# STC31_Breakout.net
KiCad netlist of a schematic drawn in EAGLE
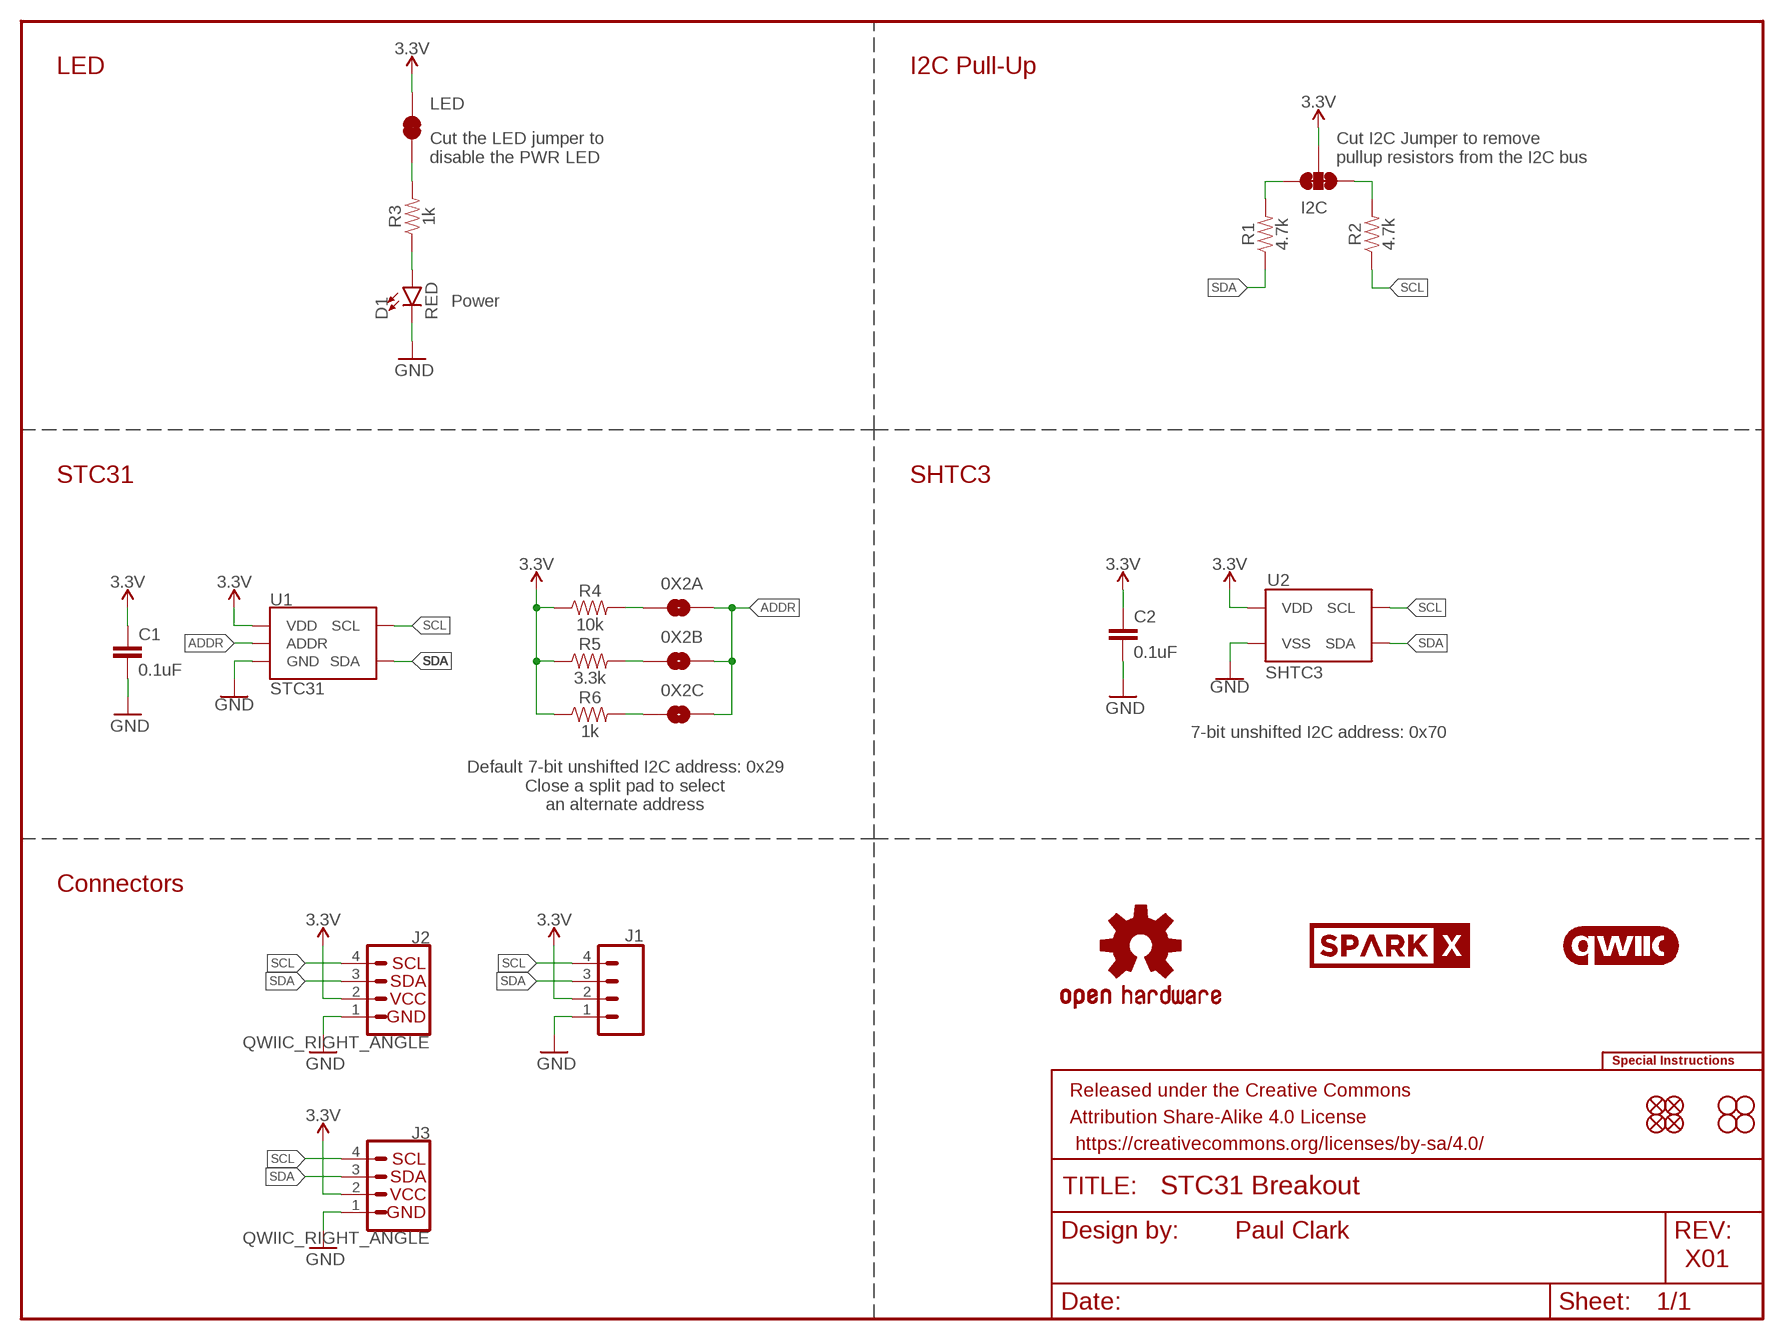
[diagram p0: schematic, sheet 1]

(export (version "E")
  (design (tool "Eeschema 10.0.6"))
  (components
    (comp (ref "0X2A")
      (value "JUMPER-SMT_2_NO_SILK")
      (footprint "eagle-import:SMT-JUMPER_2_NO_SILK")
      (libsource (lib "eagle-import") (part "JUMPER-SMT_2_NO_SILK"))
    )
    (comp (ref "0X2B")
      (value "JUMPER-SMT_2_NO_SILK")
      (footprint "eagle-import:SMT-JUMPER_2_NO_SILK")
      (libsource (lib "eagle-import") (part "JUMPER-SMT_2_NO_SILK"))
    )
    (comp (ref "0X2C")
      (value "JUMPER-SMT_2_NO_SILK")
      (footprint "eagle-import:SMT-JUMPER_2_NO_SILK")
      (libsource (lib "eagle-import") (part "JUMPER-SMT_2_NO_SILK"))
    )
    (comp (ref "C1")
      (value "0.1uF")
      (footprint "eagle-import:0603")
      (libsource (lib "eagle-import") (part "0.1UF-0603-25V-5%"))
    )
    (comp (ref "C2")
      (value "0.1uF")
      (footprint "eagle-import:0603")
      (libsource (lib "eagle-import") (part "0.1UF-0603-25V-5%"))
    )
    (comp (ref "D1")
      (value "RED")
      (footprint "eagle-import:LED-0603")
      (libsource (lib "eagle-import") (part "LED-RED0603"))
    )
    (comp (ref "FRAME1")
      (value "FRAME-LETTER")
      (footprint "eagle-import:CREATIVE_COMMONS")
      (libsource (lib "eagle-import") (part "FRAME-LETTER"))
    )
    (comp (ref "I2C")
      (value "JUMPER-SMT_3_2-NC_TRACE_SILK")
      (footprint "eagle-import:SMT-JUMPER_3_2-NC_TRACE_SILK")
      (libsource (lib "eagle-import") (part "JUMPER-SMT_3_2-NC_TRACE_SILK"))
    )
    (comp (ref "J1")
      (value "CONN_041X04_NO_SILK")
      (footprint "eagle-import:1X04_NO_SILK")
      (libsource (lib "eagle-import") (part "CONN_041X04_NO_SILK"))
    )
    (comp (ref "J2")
      (value "QWIIC_RIGHT_ANGLE")
      (footprint "eagle-import:JST04_1MM_RA")
      (libsource (lib "eagle-import") (part "QWIIC_CONNECTORJS-1MM"))
    )
    (comp (ref "J3")
      (value "QWIIC_RIGHT_ANGLE")
      (footprint "eagle-import:JST04_1MM_RA")
      (libsource (lib "eagle-import") (part "QWIIC_CONNECTORJS-1MM"))
    )
    (comp (ref "JP1")
      (value "FIDUCIAL1X2")
      (footprint "eagle-import:FIDUCIAL-1X2")
      (libsource (lib "eagle-import") (part "FIDUCIAL1X2"))
    )
    (comp (ref "JP2")
      (value "FIDUCIAL1X2")
      (footprint "eagle-import:FIDUCIAL-1X2")
      (libsource (lib "eagle-import") (part "FIDUCIAL1X2"))
    )
    (comp (ref "JP3")
      (value "STAND-OFF")
      (footprint "eagle-import:STAND-OFF")
      (libsource (lib "eagle-import") (part "STAND-OFF"))
    )
    (comp (ref "JP4")
      (value "STAND-OFF")
      (footprint "eagle-import:STAND-OFF")
      (libsource (lib "eagle-import") (part "STAND-OFF"))
    )
    (comp (ref "JP5")
      (value "FIDUCIAL1X2")
      (footprint "eagle-import:FIDUCIAL-1X2")
      (libsource (lib "eagle-import") (part "FIDUCIAL1X2"))
    )
    (comp (ref "JP6")
      (value "FIDUCIAL1X2")
      (footprint "eagle-import:FIDUCIAL-1X2")
      (libsource (lib "eagle-import") (part "FIDUCIAL1X2"))
    )
    (comp (ref "JP7")
      (value "STAND-OFF")
      (footprint "eagle-import:STAND-OFF")
      (libsource (lib "eagle-import") (part "STAND-OFF"))
    )
    (comp (ref "JP8")
      (value "STAND-OFF")
      (footprint "eagle-import:STAND-OFF")
      (libsource (lib "eagle-import") (part "STAND-OFF"))
    )
    (comp (ref "LED")
      (value "JUMPER-SMT_2_NC_TRACE_SILK")
      (footprint "eagle-import:SMT-JUMPER_2_NC_TRACE_SILK")
      (libsource (lib "eagle-import") (part "JUMPER-SMT_2_NC_TRACE_SILK"))
    )
    (comp (ref "LOGO1")
      (value "SPECIAL_INSTRUCTIONS-ORDERING")
      (footprint "eagle-import:ORDERING_INSTRUCTIONS")
      (libsource (lib "eagle-import") (part "SPECIAL_INSTRUCTIONS-ORDERING"))
    )
    (comp (ref "LOGO2")
      (value "QWIIC_LOGO_5MM")
      (footprint "eagle-import:QWIIC_5MM")
      (libsource (lib "eagle-import") (part "QWIIC_LOGO_5MM"))
    )
    (comp (ref "LOGO5")
      (value "OSHW-LOGOS")
      (footprint "eagle-import:OSHW-LOGO-S")
      (libsource (lib "eagle-import") (part "OSHW-LOGOS"))
    )
    (comp (ref "R1")
      (value "4.7k")
      (footprint "eagle-import:0603")
      (libsource (lib "eagle-import") (part "4.7KOHM-0603-1/10W-1%"))
    )
    (comp (ref "R2")
      (value "4.7k")
      (footprint "eagle-import:0603")
      (libsource (lib "eagle-import") (part "4.7KOHM-0603-1/10W-1%"))
    )
    (comp (ref "R3")
      (value "1k")
      (footprint "eagle-import:0603")
      (libsource (lib "eagle-import") (part "1KOHM-0603-1/10W-1%"))
    )
    (comp (ref "R4")
      (value "10k")
      (footprint "eagle-import:0603")
      (libsource (lib "eagle-import") (part "10KOHM-0603-1/10W-1%"))
    )
    (comp (ref "R5")
      (value "3.3k")
      (footprint "eagle-import:0603")
      (libsource (lib "eagle-import") (part "3.3KOHM-0603-1/10W-1%"))
    )
    (comp (ref "R6")
      (value "1k")
      (footprint "eagle-import:0603")
      (libsource (lib "eagle-import") (part "1KOHM-0603-1/10W-1%"))
    )
    (comp (ref "U$10")
      (value "SPARKX-LOGO3")
      (footprint "eagle-import:SPARKX-SMALL")
      (libsource (lib "eagle-import") (part "SPARKX-LOGO3"))
    )
    (comp (ref "U$18")
      (value "SPARKX-LOGO3")
      (footprint "eagle-import:SPARKX-SMALL")
      (libsource (lib "eagle-import") (part "SPARKX-LOGO3"))
    )
    (comp (ref "U1")
      (value "STC31")
      (footprint "eagle-import:STC31")
      (fields (field (name "MANU_PART") "STC31-R3"))
      (libsource (lib "eagle-import") (part "STC31"))
    )
    (comp (ref "U2")
      (value "SHTC3")
      (footprint "eagle-import:SHTC3")
      (libsource (lib "eagle-import") (part "SHTC3"))
    )
  )
  (nets
    (net (code "1") (name "3.3V") (class "Default")
      (node (ref "C1") (pin "1") (pinfunction "1_1") (pintype "passive"))
      (node (ref "C2") (pin "1") (pinfunction "1_1") (pintype "passive"))
      (node (ref "I2C") (pin "2") (pinfunction "2_2") (pintype "passive"))
      (node (ref "J1") (pin "2") (pinfunction "2_2") (pintype "passive"))
      (node (ref "J2") (pin "2") (pinfunction "2_2") (pintype "power_in"))
      (node (ref "J3") (pin "2") (pinfunction "2_2") (pintype "power_in"))
      (node (ref "LED") (pin "2") (pinfunction "2_2") (pintype "passive"))
      (node (ref "R4") (pin "1") (pinfunction "1_1") (pintype "passive"))
      (node (ref "R5") (pin "1") (pinfunction "1_1") (pintype "passive"))
      (node (ref "R6") (pin "1") (pinfunction "1_1") (pintype "passive"))
      (node (ref "U1") (pin "6") (pinfunction "VDD_6") (pintype "power_in"))
      (node (ref "U2") (pin "1") (pinfunction "VDD_1") (pintype "bidirectional"))
    )
    (net (code "2") (name "ADDR") (class "Default")
      (node (ref "0X2A") (pin "2") (pinfunction "2_2") (pintype "passive"))
      (node (ref "0X2B") (pin "2") (pinfunction "2_2") (pintype "passive"))
      (node (ref "0X2C") (pin "2") (pinfunction "2_2") (pintype "passive"))
      (node (ref "U1") (pin "3") (pinfunction "ADDR_3") (pintype "bidirectional"))
    )
    (net (code "3") (name "GND") (class "Default")
      (node (ref "C1") (pin "2") (pinfunction "2_2") (pintype "passive"))
      (node (ref "C2") (pin "2") (pinfunction "2_2") (pintype "passive"))
      (node (ref "D1") (pin "C") (pinfunction "C_C") (pintype "passive"))
      (node (ref "J1") (pin "1") (pinfunction "1_1") (pintype "passive"))
      (node (ref "J2") (pin "1") (pinfunction "1_1") (pintype "power_in"))
      (node (ref "J3") (pin "1") (pinfunction "1_1") (pintype "power_in"))
      (node (ref "U1") (pin "1") (pinfunction "GND_1") (pintype "power_in"))
      (node (ref "U1") (pin "11") (pinfunction "GND_11") (pintype "power_in"))
      (node (ref "U1") (pin "5") (pinfunction "GND_5") (pintype "power_in"))
      (node (ref "U1") (pin "9") (pinfunction "GND_9") (pintype "power_in"))
      (node (ref "U1") (pin "DIEPAD") (pinfunction "GND_DIEPAD") (pintype "power_in"))
      (node (ref "U2") (pin "4") (pinfunction "VSS_4") (pintype "bidirectional"))
      (node (ref "U2") (pin "5") (pinfunction "VSS_5") (pintype "bidirectional"))
    )
    (net (code "4") (name "Net-(0X2A-Pad1)") (class "Default")
      (node (ref "0X2A") (pin "1") (pinfunction "1_1") (pintype "passive"))
      (node (ref "R4") (pin "2") (pinfunction "2_2") (pintype "passive"))
    )
    (net (code "5") (name "Net-(0X2B-Pad1)") (class "Default")
      (node (ref "0X2B") (pin "1") (pinfunction "1_1") (pintype "passive"))
      (node (ref "R5") (pin "2") (pinfunction "2_2") (pintype "passive"))
    )
    (net (code "6") (name "Net-(0X2C-Pad1)") (class "Default")
      (node (ref "0X2C") (pin "1") (pinfunction "1_1") (pintype "passive"))
      (node (ref "R6") (pin "2") (pinfunction "2_2") (pintype "passive"))
    )
    (net (code "7") (name "Net-(D1-PadA)") (class "Default")
      (node (ref "D1") (pin "A") (pinfunction "A_A") (pintype "passive"))
      (node (ref "R3") (pin "1") (pinfunction "1_1") (pintype "passive"))
    )
    (net (code "8") (name "Net-(I2C-Pad1)") (class "Default")
      (node (ref "I2C") (pin "1") (pinfunction "1_1") (pintype "passive"))
      (node (ref "R2") (pin "2") (pinfunction "2_2") (pintype "passive"))
    )
    (net (code "9") (name "Net-(I2C-Pad3)") (class "Default")
      (node (ref "I2C") (pin "3") (pinfunction "3_3") (pintype "passive"))
      (node (ref "R1") (pin "2") (pinfunction "2_2") (pintype "passive"))
    )
    (net (code "10") (name "Net-(LED-Pad1)") (class "Default")
      (node (ref "LED") (pin "1") (pinfunction "1_1") (pintype "passive"))
      (node (ref "R3") (pin "2") (pinfunction "2_2") (pintype "passive"))
    )
    (net (code "11") (name "SCL") (class "Default")
      (node (ref "J1") (pin "4") (pinfunction "4_4") (pintype "passive"))
      (node (ref "J2") (pin "4") (pinfunction "4_4") (pintype "passive"))
      (node (ref "J3") (pin "4") (pinfunction "4_4") (pintype "passive"))
      (node (ref "R2") (pin "1") (pinfunction "1_1") (pintype "passive"))
      (node (ref "U1") (pin "4") (pinfunction "SCL_4") (pintype "bidirectional"))
      (node (ref "U2") (pin "2") (pinfunction "SCL_2") (pintype "bidirectional"))
    )
    (net (code "12") (name "SDA") (class "Default")
      (node (ref "J1") (pin "3") (pinfunction "3_3") (pintype "passive"))
      (node (ref "J2") (pin "3") (pinfunction "3_3") (pintype "passive"))
      (node (ref "J3") (pin "3") (pinfunction "3_3") (pintype "passive"))
      (node (ref "R1") (pin "1") (pinfunction "1_1") (pintype "passive"))
      (node (ref "U1") (pin "7") (pinfunction "SDA_7") (pintype "bidirectional"))
      (node (ref "U2") (pin "3") (pinfunction "SDA_3") (pintype "bidirectional"))
    )
  )
)
